# ESC.net
KiCad netlist of a schematic drawn in Altium Designer
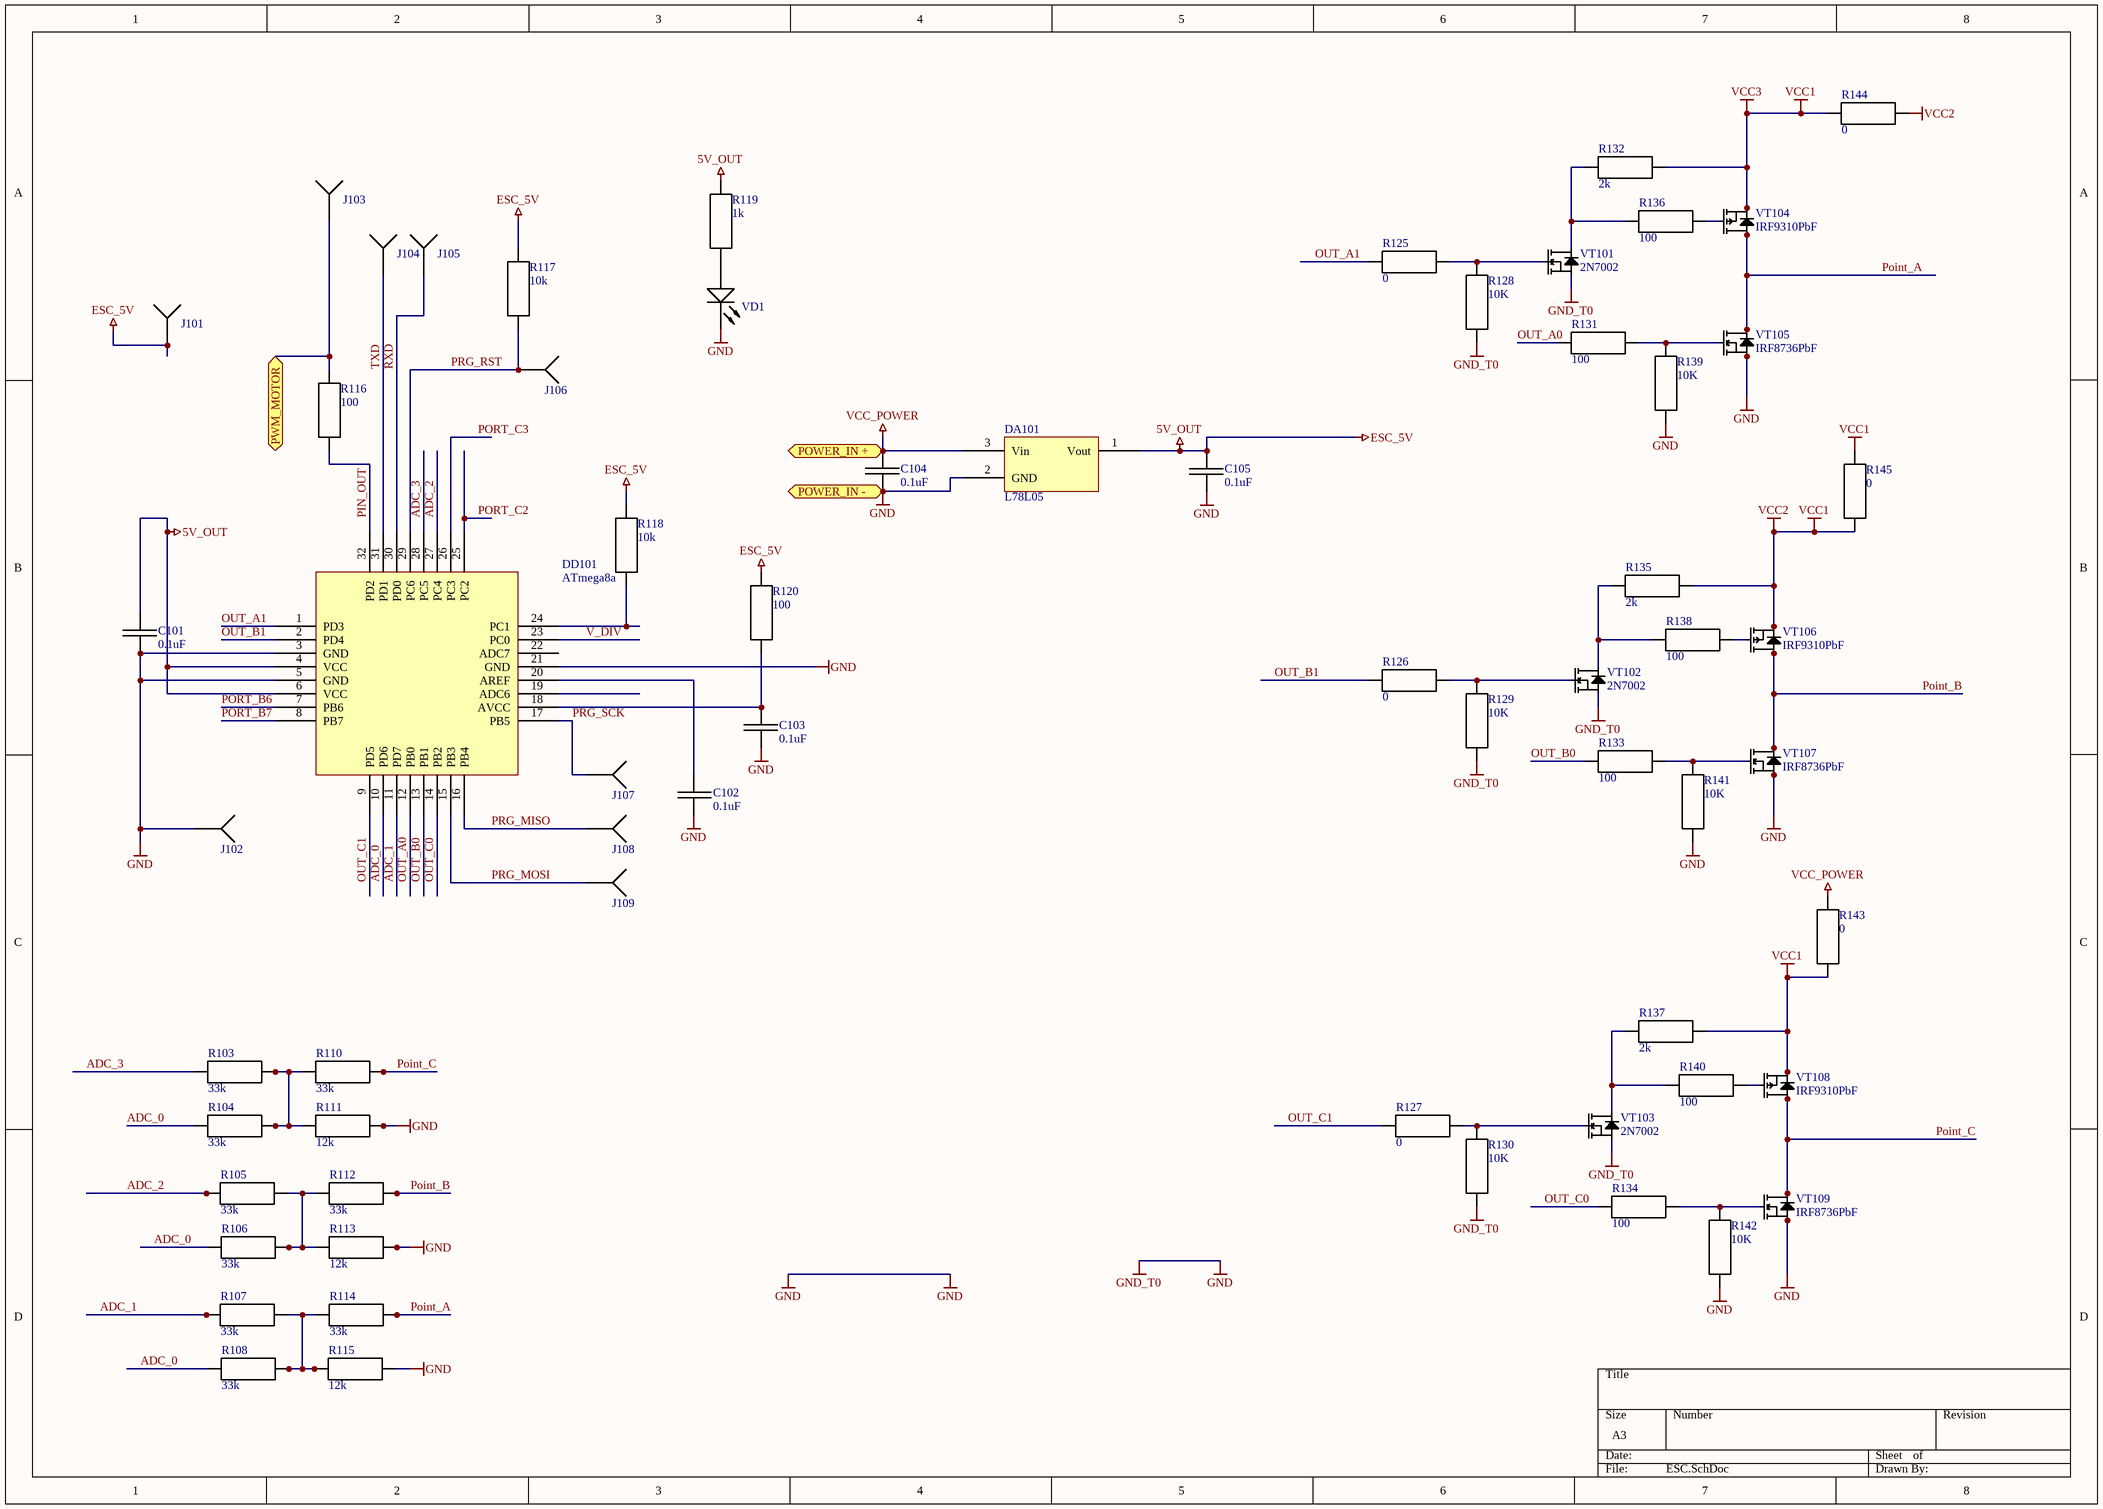
[diagram p0: ESC.SchDoc]

(export (version "E")
  (design (tool "Eeschema 10.0.6"))
  (components
    (comp (ref "C101")
      (value "0.1uF")
      (footprint "CAP0805")
      (fields (field (name "VOLTAGE") "50V"))
      (libsource (lib "Schlib1") (part "Capacitor"))
    )
    (comp (ref "C102")
      (value "0.1uF")
      (footprint "CAP0805")
      (fields (field (name "VOLTAGE") "50V"))
      (libsource (lib "Schlib1") (part "Capacitor"))
    )
    (comp (ref "C103")
      (value "0.1uF")
      (footprint "CAP0805")
      (fields (field (name "VOLTAGE") "50V"))
      (libsource (lib "Schlib1") (part "Capacitor"))
    )
    (comp (ref "C104")
      (value "0.1uF")
      (footprint "CAP0805")
      (fields (field (name "VOLTAGE") "50V"))
      (libsource (lib "Schlib1") (part "Capacitor"))
    )
    (comp (ref "C105")
      (value "0.1uF")
      (footprint "CAP0805")
      (fields (field (name "VOLTAGE") "50V"))
      (libsource (lib "Schlib1") (part "Capacitor"))
    )
    (comp (ref "DA101")
      (value "L78L05")
      (footprint "SOT89")
      (description "LDO")
      (libsource (lib "Schlib1") (part "DA-L78L05"))
    )
    (comp (ref "DD101")
      (value "ATmega8a")
      (footprint "ATMEGA8A")
      (description "MCU 8MHz")
      (libsource (lib "Schlib1") (part "ATmega8a"))
    )
    (comp (ref "J101") (value "X-Socket") (footprint "Socket") (libsource (lib "Schlib1") (part "X-Socket")))
    (comp (ref "J102") (value "X-Socket") (footprint "Socket") (libsource (lib "Schlib1") (part "X-Socket")))
    (comp (ref "J103") (value "X-Socket") (footprint "Socket") (libsource (lib "Schlib1") (part "X-Socket")))
    (comp (ref "J104") (value "X-Socket") (footprint "Socket") (libsource (lib "Schlib1") (part "X-Socket")))
    (comp (ref "J105") (value "X-Socket") (footprint "Socket") (libsource (lib "Schlib1") (part "X-Socket")))
    (comp (ref "J106") (value "X-Socket") (footprint "Socket") (libsource (lib "Schlib1") (part "X-Socket")))
    (comp (ref "J107") (value "X-Socket") (footprint "Socket") (libsource (lib "Schlib1") (part "X-Socket")))
    (comp (ref "J108") (value "X-Socket") (footprint "Socket") (libsource (lib "Schlib1") (part "X-Socket")))
    (comp (ref "J109") (value "X-Socket") (footprint "Socket") (libsource (lib "Schlib1") (part "X-Socket")))
    (comp (ref "R103") (value "33k") (footprint "RES0603") (libsource (lib "") (part "Resistor_2")))
    (comp (ref "R104") (value "33k") (footprint "RES0603") (libsource (lib "") (part "Resistor_2")))
    (comp (ref "R105") (value "33k") (footprint "RES0603") (libsource (lib "") (part "Resistor_2")))
    (comp (ref "R106") (value "33k") (footprint "RES0603") (libsource (lib "") (part "Resistor_2")))
    (comp (ref "R107") (value "33k") (footprint "RES0603") (libsource (lib "") (part "Resistor_2")))
    (comp (ref "R108") (value "33k") (footprint "RES0603") (libsource (lib "") (part "Resistor_2")))
    (comp (ref "R110") (value "33k") (footprint "RES0603") (libsource (lib "") (part "Resistor_2")))
    (comp (ref "R111") (value "12k") (footprint "RES0603") (libsource (lib "") (part "Resistor_2")))
    (comp (ref "R112") (value "33k") (footprint "RES0603") (libsource (lib "") (part "Resistor_2")))
    (comp (ref "R113") (value "12k") (footprint "RES0603") (libsource (lib "") (part "Resistor_2")))
    (comp (ref "R114") (value "33k") (footprint "RES0603") (libsource (lib "") (part "Resistor_2")))
    (comp (ref "R115") (value "12k") (footprint "RES0603") (libsource (lib "") (part "Resistor_2")))
    (comp (ref "R116") (value "100") (footprint "RES0805") (libsource (lib "Schlib1") (part "Resistor")))
    (comp (ref "R117") (value "10k") (footprint "RES0805") (libsource (lib "") (part "Resistor_1")))
    (comp (ref "R118") (value "10k") (footprint "RES0805") (libsource (lib "") (part "Resistor_1")))
    (comp (ref "R119") (value "1k") (footprint "RES0603") (libsource (lib "Schlib1") (part "Resistor")))
    (comp (ref "R120") (value "100") (footprint "RES0603") (libsource (lib "") (part "Resistor_1")))
    (comp (ref "R125") (value "0") (footprint "RES1206") (libsource (lib "") (part "Resistor_2")))
    (comp (ref "R126") (value "0") (footprint "RES1206") (libsource (lib "") (part "Resistor_2")))
    (comp (ref "R127") (value "0") (footprint "RES0805") (libsource (lib "") (part "Resistor_2")))
    (comp (ref "R128") (value "10K") (footprint "RES0603") (libsource (lib "") (part "Resistor_1")))
    (comp (ref "R129") (value "10K") (footprint "RES0603") (libsource (lib "") (part "Resistor_1")))
    (comp (ref "R130") (value "10K") (footprint "RES0603") (libsource (lib "") (part "Resistor_1")))
    (comp (ref "R131") (value "100") (footprint "RES0603") (libsource (lib "") (part "Resistor_3")))
    (comp (ref "R132") (value "2k") (footprint "RES0603") (libsource (lib "") (part "Resistor_2")))
    (comp (ref "R133") (value "100") (footprint "RES0603") (libsource (lib "") (part "Resistor_3")))
    (comp (ref "R134") (value "100") (footprint "RES0603") (libsource (lib "") (part "Resistor_3")))
    (comp (ref "R135") (value "2k") (footprint "RES0603") (libsource (lib "") (part "Resistor_2")))
    (comp (ref "R136") (value "100") (footprint "RES0603") (libsource (lib "") (part "Resistor_3")))
    (comp (ref "R137") (value "2k") (footprint "RES0603") (libsource (lib "") (part "Resistor_2")))
    (comp (ref "R138") (value "100") (footprint "RES0603") (libsource (lib "") (part "Resistor_3")))
    (comp (ref "R139") (value "10K") (footprint "RES0603") (libsource (lib "") (part "Resistor_1")))
    (comp (ref "R140") (value "100") (footprint "RES0603") (libsource (lib "") (part "Resistor_3")))
    (comp (ref "R141") (value "10K") (footprint "RES0603") (libsource (lib "") (part "Resistor_1")))
    (comp (ref "R142") (value "10K") (footprint "RES0603") (libsource (lib "") (part "Resistor_1")))
    (comp (ref "R143") (value "0") (footprint "RES2512") (libsource (lib "") (part "Resistor_1")))
    (comp (ref "R144") (value "0") (footprint "RES1206") (libsource (lib "") (part "Resistor_3")))
    (comp (ref "R145") (value "0") (footprint "RES1206") (libsource (lib "Schlib1") (part "Resistor")))
    (comp (ref "VD1")
      (value "KP-1608SURC")
      (footprint "Diode 1608")
      (libsource (lib "Schlib1") (part "LED_0603"))
    )
    (comp (ref "VT101") (value "2N7002") (footprint "SOT23") (libsource (lib "Schlib1") (part "2N7002")))
    (comp (ref "VT102") (value "2N7002") (footprint "SOT23") (libsource (lib "Schlib1") (part "2N7002")))
    (comp (ref "VT103") (value "2N7002") (footprint "SOT23") (libsource (lib "Schlib1") (part "2N7002")))
    (comp (ref "VT104")
      (value "IRF9310PbF")
      (footprint "SO-8 IRF...")
      (description "P-MOSFET -20A")
      (libsource (lib "Schlib1") (part "IRF9310PbF"))
    )
    (comp (ref "VT105")
      (value "IRF8736PbF")
      (footprint "SO-8 IRF...")
      (description "N-MOSFET 18A")
      (libsource (lib "Schlib1") (part "IRF8736PbF"))
    )
    (comp (ref "VT106")
      (value "IRF9310PbF")
      (footprint "SO-8 IRF...")
      (description "P-MOSFET -20A")
      (libsource (lib "Schlib1") (part "IRF9310PbF"))
    )
    (comp (ref "VT107")
      (value "IRF8736PbF")
      (footprint "SO-8 IRF...")
      (description "N-MOSFET 18A")
      (libsource (lib "Schlib1") (part "IRF8736PbF"))
    )
    (comp (ref "VT108")
      (value "IRF9310PbF")
      (footprint "SO-8 IRF...")
      (description "P-MOSFET -20A")
      (libsource (lib "Schlib1") (part "IRF9310PbF"))
    )
    (comp (ref "VT109")
      (value "IRF8736PbF")
      (footprint "SO-8 IRF...")
      (description "N-MOSFET 18A")
      (libsource (lib "Schlib1") (part "IRF8736PbF"))
    )
  )
  (nets
    (net (code "1") (name "/ADC_0") (class "Default")
      (node (ref "DD101") (pin "10") (pinfunction "PD6_10") (pintype "passive"))
      (node (ref "R104") (pin "2") (pinfunction "2_2") (pintype "passive"))
      (node (ref "R106") (pin "2") (pinfunction "2_2") (pintype "passive"))
      (node (ref "R108") (pin "2") (pinfunction "2_2") (pintype "passive"))
    )
    (net (code "2") (name "/ADC_1") (class "Default")
      (node (ref "DD101") (pin "11") (pinfunction "PD7_11") (pintype "passive"))
      (node (ref "R107") (pin "2") (pinfunction "2_2") (pintype "passive"))
    )
    (net (code "3") (name "/ADC_2") (class "Default")
      (node (ref "DD101") (pin "27") (pinfunction "PC4_27") (pintype "passive"))
      (node (ref "R105") (pin "2") (pinfunction "2_2") (pintype "passive"))
    )
    (net (code "4") (name "/ADC_3") (class "Default")
      (node (ref "DD101") (pin "28") (pinfunction "PC5_28") (pintype "passive"))
      (node (ref "R103") (pin "2") (pinfunction "2_2") (pintype "passive"))
    )
    (net (code "5") (name "/OUT_A0") (class "Default")
      (node (ref "DD101") (pin "12") (pinfunction "PB0_12") (pintype "passive"))
      (node (ref "R131") (pin "1") (pinfunction "1_1") (pintype "passive"))
    )
    (net (code "6") (name "/OUT_A1") (class "Default")
      (node (ref "DD101") (pin "1") (pinfunction "PD3_1") (pintype "passive"))
      (node (ref "R125") (pin "2") (pinfunction "2_2") (pintype "passive"))
    )
    (net (code "7") (name "/OUT_B0") (class "Default")
      (node (ref "DD101") (pin "13") (pinfunction "PB1_13") (pintype "passive"))
      (node (ref "R133") (pin "1") (pinfunction "1_1") (pintype "passive"))
    )
    (net (code "8") (name "/OUT_B1") (class "Default")
      (node (ref "DD101") (pin "2") (pinfunction "PD4_2") (pintype "passive"))
      (node (ref "R126") (pin "2") (pinfunction "2_2") (pintype "passive"))
    )
    (net (code "9") (name "/OUT_C0") (class "Default")
      (node (ref "DD101") (pin "14") (pinfunction "PB2_14") (pintype "passive"))
      (node (ref "R134") (pin "1") (pinfunction "1_1") (pintype "passive"))
    )
    (net (code "10") (name "/OUT_C1") (class "Default")
      (node (ref "DD101") (pin "9") (pinfunction "PD5_9") (pintype "passive"))
      (node (ref "R127") (pin "2") (pinfunction "2_2") (pintype "passive"))
    )
    (net (code "11") (name "/PIN_OUT") (class "Default")
      (node (ref "DD101") (pin "32") (pinfunction "PD2_32") (pintype "passive"))
      (node (ref "R116") (pin "2") (pinfunction "2_2") (pintype "passive"))
    )
    (net (code "12") (name "/PORT_B6") (class "Default")
      (node (ref "DD101") (pin "7") (pinfunction "PB6_7") (pintype "passive"))
    )
    (net (code "13") (name "/PORT_B7") (class "Default")
      (node (ref "DD101") (pin "8") (pinfunction "PB7_8") (pintype "passive"))
    )
    (net (code "14") (name "/PORT_C2") (class "Default")
      (node (ref "DD101") (pin "25") (pinfunction "PC2_25") (pintype "passive"))
    )
    (net (code "15") (name "/PORT_C3") (class "Default")
      (node (ref "DD101") (pin "26") (pinfunction "PC3_26") (pintype "passive"))
    )
    (net (code "16") (name "/PRG_MISO") (class "Default")
      (node (ref "DD101") (pin "16") (pinfunction "PB4_16") (pintype "passive"))
      (node (ref "J108") (pin "1") (pinfunction "1_1") (pintype "passive"))
    )
    (net (code "17") (name "/PRG_MOSI") (class "Default")
      (node (ref "DD101") (pin "15") (pinfunction "PB3_15") (pintype "passive"))
      (node (ref "J109") (pin "1") (pinfunction "1_1") (pintype "passive"))
    )
    (net (code "18") (name "/PRG_RST") (class "Default")
      (node (ref "DD101") (pin "29") (pinfunction "PC6_29") (pintype "passive"))
      (node (ref "J106") (pin "1") (pinfunction "1_1") (pintype "passive"))
      (node (ref "R117") (pin "1") (pinfunction "1_1") (pintype "passive"))
    )
    (net (code "19") (name "/PRG_SCK") (class "Default")
      (node (ref "DD101") (pin "17") (pinfunction "PB5_17") (pintype "passive"))
      (node (ref "J107") (pin "1") (pinfunction "1_1") (pintype "passive"))
    )
    (net (code "20") (name "/PWM_MOTOR") (class "Default")
      (node (ref "J103") (pin "1") (pinfunction "1_1") (pintype "passive"))
      (node (ref "R116") (pin "1") (pinfunction "1_1") (pintype "passive"))
    )
    (net (code "21") (name "/Point_A") (class "Default")
      (node (ref "R114") (pin "1") (pinfunction "1_1") (pintype "passive"))
      (node (ref "VT104") (pin "5") (pinfunction "D_5") (pintype "passive"))
      (node (ref "VT104") (pin "6") (pinfunction "D_6") (pintype "passive"))
      (node (ref "VT104") (pin "7") (pinfunction "D_7") (pintype "passive"))
      (node (ref "VT104") (pin "8") (pinfunction "D_8") (pintype "passive"))
      (node (ref "VT105") (pin "5") (pinfunction "D_5") (pintype "passive"))
      (node (ref "VT105") (pin "6") (pinfunction "D_6") (pintype "passive"))
      (node (ref "VT105") (pin "7") (pinfunction "D_7") (pintype "passive"))
      (node (ref "VT105") (pin "8") (pinfunction "D_8") (pintype "passive"))
    )
    (net (code "22") (name "/Point_B") (class "Default")
      (node (ref "R112") (pin "1") (pinfunction "1_1") (pintype "passive"))
      (node (ref "VT106") (pin "5") (pinfunction "D_5") (pintype "passive"))
      (node (ref "VT106") (pin "6") (pinfunction "D_6") (pintype "passive"))
      (node (ref "VT106") (pin "7") (pinfunction "D_7") (pintype "passive"))
      (node (ref "VT106") (pin "8") (pinfunction "D_8") (pintype "passive"))
      (node (ref "VT107") (pin "5") (pinfunction "D_5") (pintype "passive"))
      (node (ref "VT107") (pin "6") (pinfunction "D_6") (pintype "passive"))
      (node (ref "VT107") (pin "7") (pinfunction "D_7") (pintype "passive"))
      (node (ref "VT107") (pin "8") (pinfunction "D_8") (pintype "passive"))
    )
    (net (code "23") (name "/Point_C") (class "Default")
      (node (ref "R110") (pin "1") (pinfunction "1_1") (pintype "passive"))
      (node (ref "VT108") (pin "5") (pinfunction "D_5") (pintype "passive"))
      (node (ref "VT108") (pin "6") (pinfunction "D_6") (pintype "passive"))
      (node (ref "VT108") (pin "7") (pinfunction "D_7") (pintype "passive"))
      (node (ref "VT108") (pin "8") (pinfunction "D_8") (pintype "passive"))
      (node (ref "VT109") (pin "5") (pinfunction "D_5") (pintype "passive"))
      (node (ref "VT109") (pin "6") (pinfunction "D_6") (pintype "passive"))
      (node (ref "VT109") (pin "7") (pinfunction "D_7") (pintype "passive"))
      (node (ref "VT109") (pin "8") (pinfunction "D_8") (pintype "passive"))
    )
    (net (code "24") (name "/RXD") (class "Default")
      (node (ref "DD101") (pin "30") (pinfunction "PD0_30") (pintype "passive"))
      (node (ref "J105") (pin "1") (pinfunction "1_1") (pintype "passive"))
    )
    (net (code "25") (name "/TXD") (class "Default")
      (node (ref "DD101") (pin "31") (pinfunction "PD1_31") (pintype "passive"))
      (node (ref "J104") (pin "1") (pinfunction "1_1") (pintype "passive"))
    )
    (net (code "26") (name "/V_DIV") (class "Default")
      (node (ref "DD101") (pin "23") (pinfunction "PC0_23") (pintype "passive"))
    )
    (net (code "27") (name "5V_OUT") (class "Default")
      (node (ref "C101") (pin "1") (pinfunction "1_1") (pintype "passive"))
      (node (ref "C105") (pin "1") (pinfunction "1_1") (pintype "passive"))
      (node (ref "DA101") (pin "1") (pinfunction "Vout_1") (pintype "passive"))
      (node (ref "DD101") (pin "4") (pinfunction "VCC_4") (pintype "passive"))
      (node (ref "DD101") (pin "6") (pinfunction "VCC_6") (pintype "passive"))
      (node (ref "J101") (pin "1") (pinfunction "1_1") (pintype "passive"))
      (node (ref "R117") (pin "2") (pinfunction "2_2") (pintype "passive"))
      (node (ref "R118") (pin "2") (pinfunction "2_2") (pintype "passive"))
      (node (ref "R119") (pin "1") (pinfunction "1_1") (pintype "passive"))
      (node (ref "R120") (pin "2") (pinfunction "2_2") (pintype "passive"))
    )
    (net (code "28") (name "GND") (class "Default")
      (node (ref "C101") (pin "2") (pinfunction "2_2") (pintype "passive"))
      (node (ref "C102") (pin "1") (pinfunction "1_1") (pintype "passive"))
      (node (ref "C103") (pin "2") (pinfunction "2_2") (pintype "passive"))
      (node (ref "C104") (pin "2") (pinfunction "2_2") (pintype "passive"))
      (node (ref "C105") (pin "2") (pinfunction "2_2") (pintype "passive"))
      (node (ref "DA101") (pin "2") (pinfunction "GND_2") (pintype "passive"))
      (node (ref "DD101") (pin "21") (pinfunction "GND_21") (pintype "passive"))
      (node (ref "DD101") (pin "3") (pinfunction "GND_3") (pintype "passive"))
      (node (ref "DD101") (pin "5") (pinfunction "GND_5") (pintype "passive"))
      (node (ref "J102") (pin "1") (pinfunction "1_1") (pintype "passive"))
      (node (ref "R111") (pin "1") (pinfunction "1_1") (pintype "passive"))
      (node (ref "R113") (pin "1") (pinfunction "1_1") (pintype "passive"))
      (node (ref "R115") (pin "1") (pinfunction "1_1") (pintype "passive"))
      (node (ref "R128") (pin "1") (pinfunction "1_1") (pintype "passive"))
      (node (ref "R129") (pin "1") (pinfunction "1_1") (pintype "passive"))
      (node (ref "R130") (pin "1") (pinfunction "1_1") (pintype "passive"))
      (node (ref "R139") (pin "1") (pinfunction "1_1") (pintype "passive"))
      (node (ref "R141") (pin "1") (pinfunction "1_1") (pintype "passive"))
      (node (ref "R142") (pin "1") (pinfunction "1_1") (pintype "passive"))
      (node (ref "VD1") (pin "1") (pinfunction "1_1") (pintype "passive"))
      (node (ref "VT101") (pin "2") (pinfunction "S_2") (pintype "passive"))
      (node (ref "VT102") (pin "2") (pinfunction "S_2") (pintype "passive"))
      (node (ref "VT103") (pin "2") (pinfunction "S_2") (pintype "passive"))
      (node (ref "VT105") (pin "1") (pinfunction "S_1") (pintype "passive"))
      (node (ref "VT105") (pin "2") (pinfunction "S_2") (pintype "passive"))
      (node (ref "VT105") (pin "3") (pinfunction "S_3") (pintype "passive"))
      (node (ref "VT107") (pin "1") (pinfunction "S_1") (pintype "passive"))
      (node (ref "VT107") (pin "2") (pinfunction "S_2") (pintype "passive"))
      (node (ref "VT107") (pin "3") (pinfunction "S_3") (pintype "passive"))
      (node (ref "VT109") (pin "1") (pinfunction "S_1") (pintype "passive"))
      (node (ref "VT109") (pin "2") (pinfunction "S_2") (pintype "passive"))
      (node (ref "VT109") (pin "3") (pinfunction "S_3") (pintype "passive"))
    )
    (net (code "29") (name "Net-(DD101-AREF)") (class "Default")
      (node (ref "C102") (pin "2") (pinfunction "2_2") (pintype "passive"))
      (node (ref "DD101") (pin "20") (pinfunction "AREF_20") (pintype "passive"))
    )
    (net (code "30") (name "Net-(DD101-AVCC)") (class "Default")
      (node (ref "C103") (pin "1") (pinfunction "1_1") (pintype "passive"))
      (node (ref "DD101") (pin "18") (pinfunction "AVCC_18") (pintype "passive"))
      (node (ref "R120") (pin "1") (pinfunction "1_1") (pintype "passive"))
    )
    (net (code "31") (name "Net-(DD101-PC1)") (class "Default")
      (node (ref "DD101") (pin "24") (pinfunction "PC1_24") (pintype "passive"))
      (node (ref "R118") (pin "1") (pinfunction "1_1") (pintype "passive"))
    )
    (net (code "32") (name "Net-(R103-Pad1)") (class "Default")
      (node (ref "R103") (pin "1") (pinfunction "1_1") (pintype "passive"))
      (node (ref "R104") (pin "1") (pinfunction "1_1") (pintype "passive"))
      (node (ref "R110") (pin "2") (pinfunction "2_2") (pintype "passive"))
      (node (ref "R111") (pin "2") (pinfunction "2_2") (pintype "passive"))
    )
    (net (code "33") (name "Net-(R105-Pad1)") (class "Default")
      (node (ref "R105") (pin "1") (pinfunction "1_1") (pintype "passive"))
      (node (ref "R106") (pin "1") (pinfunction "1_1") (pintype "passive"))
      (node (ref "R112") (pin "2") (pinfunction "2_2") (pintype "passive"))
      (node (ref "R113") (pin "2") (pinfunction "2_2") (pintype "passive"))
    )
    (net (code "34") (name "Net-(R107-Pad1)") (class "Default")
      (node (ref "R107") (pin "1") (pinfunction "1_1") (pintype "passive"))
      (node (ref "R108") (pin "1") (pinfunction "1_1") (pintype "passive"))
      (node (ref "R114") (pin "2") (pinfunction "2_2") (pintype "passive"))
      (node (ref "R115") (pin "2") (pinfunction "2_2") (pintype "passive"))
    )
    (net (code "35") (name "Net-(R119-Pad2)") (class "Default")
      (node (ref "R119") (pin "2") (pinfunction "2_2") (pintype "passive"))
      (node (ref "VD1") (pin "2") (pinfunction "2_2") (pintype "passive"))
    )
    (net (code "36") (name "Net-(VT101-D)") (class "Default")
      (node (ref "R132") (pin "2") (pinfunction "2_2") (pintype "passive"))
      (node (ref "R136") (pin "1") (pinfunction "1_1") (pintype "passive"))
      (node (ref "VT101") (pin "3") (pinfunction "D_3") (pintype "passive"))
    )
    (net (code "37") (name "Net-(VT101-G)") (class "Default")
      (node (ref "R125") (pin "1") (pinfunction "1_1") (pintype "passive"))
      (node (ref "R128") (pin "2") (pinfunction "2_2") (pintype "passive"))
      (node (ref "VT101") (pin "1") (pinfunction "G_1") (pintype "passive"))
    )
    (net (code "38") (name "Net-(VT102-D)") (class "Default")
      (node (ref "R135") (pin "2") (pinfunction "2_2") (pintype "passive"))
      (node (ref "R138") (pin "1") (pinfunction "1_1") (pintype "passive"))
      (node (ref "VT102") (pin "3") (pinfunction "D_3") (pintype "passive"))
    )
    (net (code "39") (name "Net-(VT102-G)") (class "Default")
      (node (ref "R126") (pin "1") (pinfunction "1_1") (pintype "passive"))
      (node (ref "R129") (pin "2") (pinfunction "2_2") (pintype "passive"))
      (node (ref "VT102") (pin "1") (pinfunction "G_1") (pintype "passive"))
    )
    (net (code "40") (name "Net-(VT103-D)") (class "Default")
      (node (ref "R137") (pin "2") (pinfunction "2_2") (pintype "passive"))
      (node (ref "R140") (pin "1") (pinfunction "1_1") (pintype "passive"))
      (node (ref "VT103") (pin "3") (pinfunction "D_3") (pintype "passive"))
    )
    (net (code "41") (name "Net-(VT103-G)") (class "Default")
      (node (ref "R127") (pin "1") (pinfunction "1_1") (pintype "passive"))
      (node (ref "R130") (pin "2") (pinfunction "2_2") (pintype "passive"))
      (node (ref "VT103") (pin "1") (pinfunction "G_1") (pintype "passive"))
    )
    (net (code "42") (name "Net-(VT104-G)") (class "Default")
      (node (ref "R136") (pin "2") (pinfunction "2_2") (pintype "passive"))
      (node (ref "VT104") (pin "4") (pinfunction "G_4") (pintype "passive"))
    )
    (net (code "43") (name "Net-(VT105-G)") (class "Default")
      (node (ref "R131") (pin "2") (pinfunction "2_2") (pintype "passive"))
      (node (ref "R139") (pin "2") (pinfunction "2_2") (pintype "passive"))
      (node (ref "VT105") (pin "4") (pinfunction "G_4") (pintype "passive"))
    )
    (net (code "44") (name "Net-(VT106-G)") (class "Default")
      (node (ref "R138") (pin "2") (pinfunction "2_2") (pintype "passive"))
      (node (ref "VT106") (pin "4") (pinfunction "G_4") (pintype "passive"))
    )
    (net (code "45") (name "Net-(VT107-G)") (class "Default")
      (node (ref "R133") (pin "2") (pinfunction "2_2") (pintype "passive"))
      (node (ref "R141") (pin "2") (pinfunction "2_2") (pintype "passive"))
      (node (ref "VT107") (pin "4") (pinfunction "G_4") (pintype "passive"))
    )
    (net (code "46") (name "Net-(VT108-G)") (class "Default")
      (node (ref "R140") (pin "2") (pinfunction "2_2") (pintype "passive"))
      (node (ref "VT108") (pin "4") (pinfunction "G_4") (pintype "passive"))
    )
    (net (code "47") (name "Net-(VT109-G)") (class "Default")
      (node (ref "R134") (pin "2") (pinfunction "2_2") (pintype "passive"))
      (node (ref "R142") (pin "2") (pinfunction "2_2") (pintype "passive"))
      (node (ref "VT109") (pin "4") (pinfunction "G_4") (pintype "passive"))
    )
    (net (code "48") (name "VCC1") (class "Default")
      (node (ref "R132") (pin "1") (pinfunction "1_1") (pintype "passive"))
      (node (ref "R135") (pin "1") (pinfunction "1_1") (pintype "passive"))
      (node (ref "R137") (pin "1") (pinfunction "1_1") (pintype "passive"))
      (node (ref "R143") (pin "1") (pinfunction "1_1") (pintype "passive"))
      (node (ref "R144") (pin "1") (pinfunction "1_1") (pintype "passive"))
      (node (ref "R144") (pin "2") (pinfunction "2_2") (pintype "passive"))
      (node (ref "R145") (pin "1") (pinfunction "1_1") (pintype "passive"))
      (node (ref "R145") (pin "2") (pinfunction "2_2") (pintype "passive"))
      (node (ref "VT104") (pin "1") (pinfunction "S_1") (pintype "passive"))
      (node (ref "VT104") (pin "2") (pinfunction "S_2") (pintype "passive"))
      (node (ref "VT104") (pin "3") (pinfunction "S_3") (pintype "passive"))
      (node (ref "VT106") (pin "1") (pinfunction "S_1") (pintype "passive"))
      (node (ref "VT106") (pin "2") (pinfunction "S_2") (pintype "passive"))
      (node (ref "VT106") (pin "3") (pinfunction "S_3") (pintype "passive"))
      (node (ref "VT108") (pin "1") (pinfunction "S_1") (pintype "passive"))
      (node (ref "VT108") (pin "2") (pinfunction "S_2") (pintype "passive"))
      (node (ref "VT108") (pin "3") (pinfunction "S_3") (pintype "passive"))
    )
    (net (code "49") (name "VCC_POWER") (class "Default")
      (node (ref "C104") (pin "1") (pinfunction "1_1") (pintype "passive"))
      (node (ref "DA101") (pin "3") (pinfunction "Vin_3") (pintype "passive"))
      (node (ref "R143") (pin "2") (pinfunction "2_2") (pintype "passive"))
    )
    (net (code "50") (name "unconnected-(DD101-ADC6-Pad19)") (class "Default")
      (node (ref "DD101") (pin "19") (pinfunction "ADC6_19") (pintype "passive"))
    )
    (net (code "51") (name "unconnected-(DD101-ADC7-Pad22)") (class "Default")
      (node (ref "DD101") (pin "22") (pinfunction "ADC7_22") (pintype "passive"))
    )
  )
)
